# v0_4_6.net
KiCad netlist of a schematic drawn in EAGLE
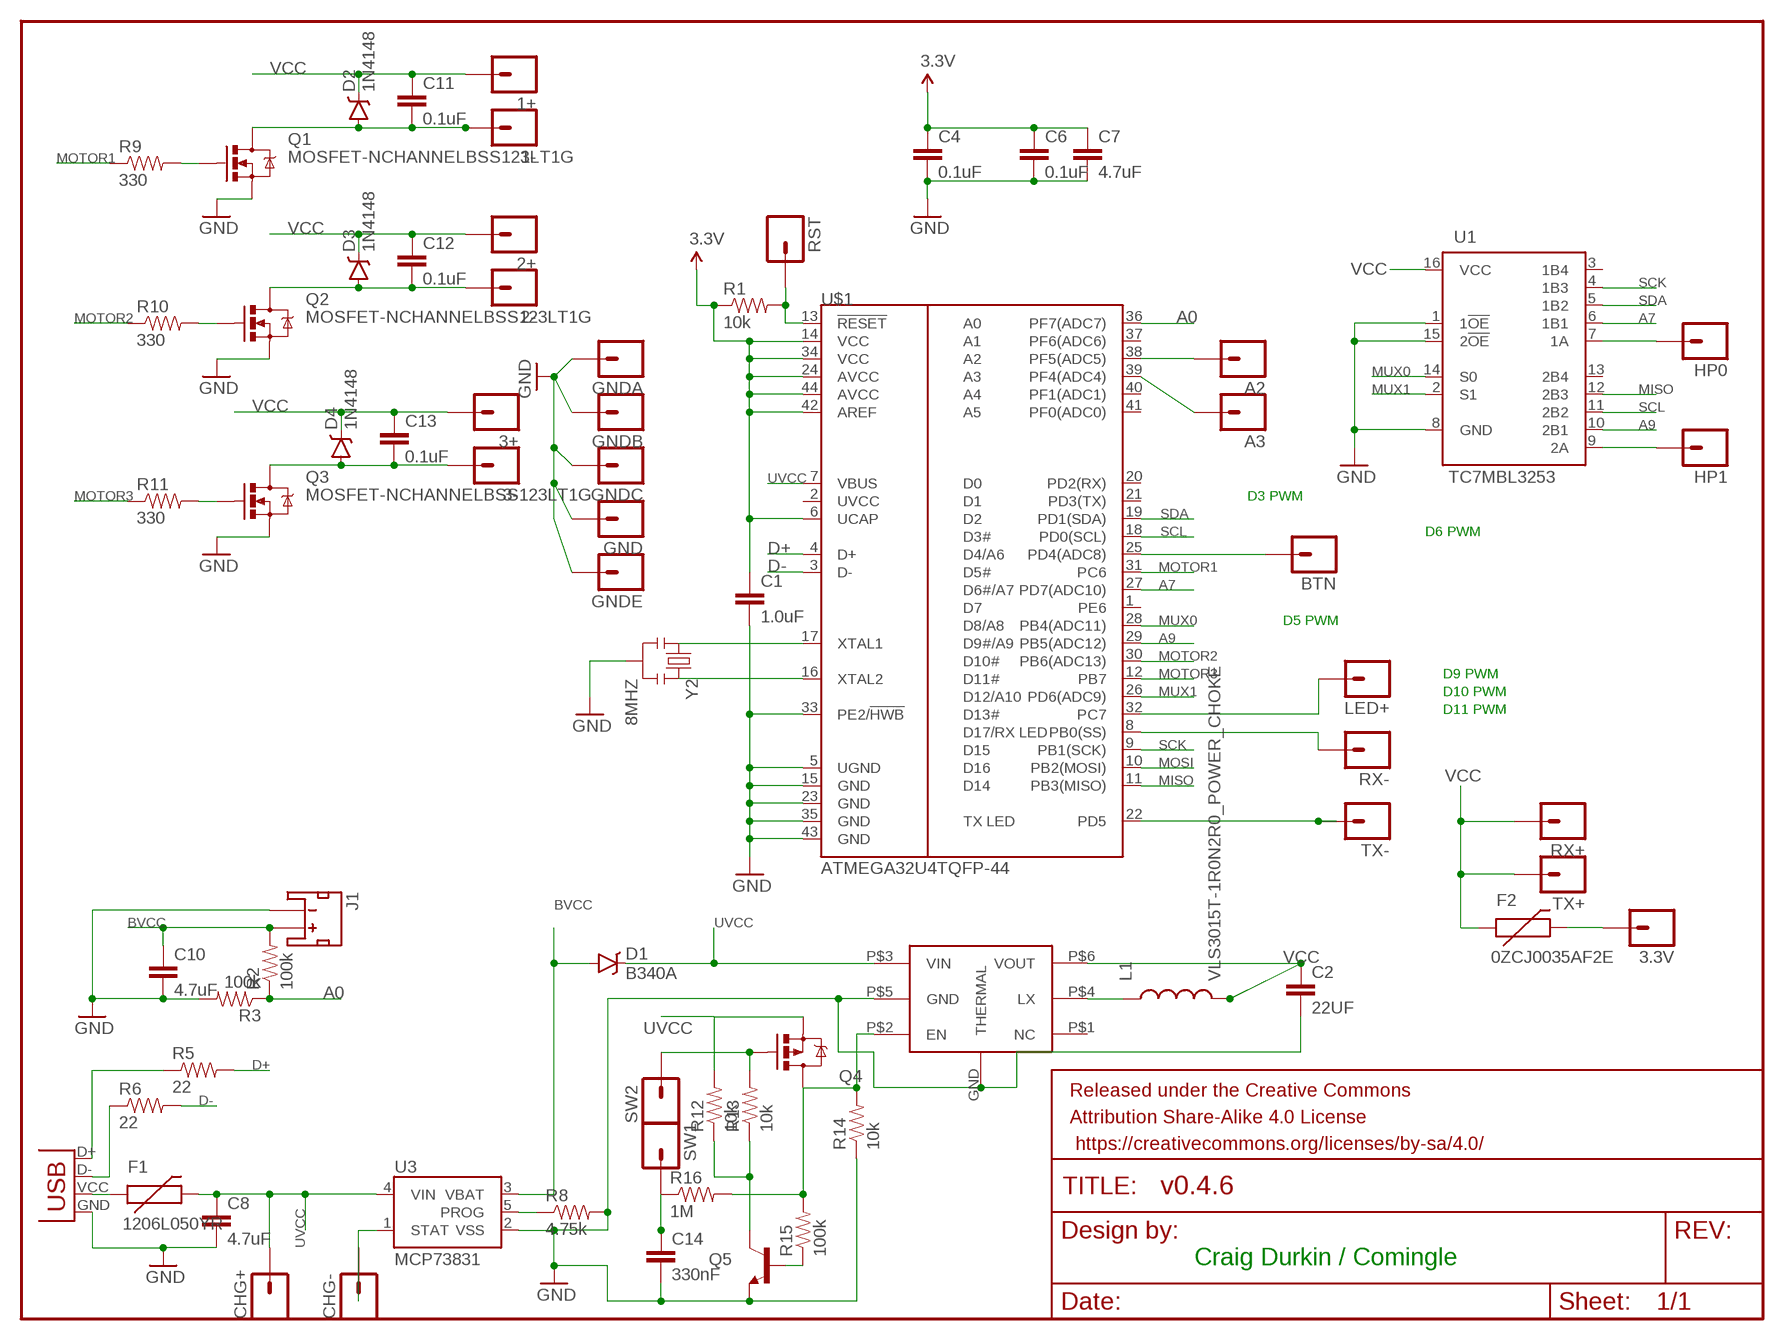
[diagram p0: schematic, sheet 1]

(export (version "E")
  (design (tool "Eeschema 10.0.6"))
  (components
    (comp (ref "1+")
      (value "M01PTH")
      (footprint "eagle-import:1X01")
      (libsource (lib "eagle-import") (part "M01PTH"))
    )
    (comp (ref "1-")
      (value "M01PTH")
      (footprint "eagle-import:1X01")
      (libsource (lib "eagle-import") (part "M01PTH"))
    )
    (comp (ref "2+")
      (value "M01PTH")
      (footprint "eagle-import:1X01")
      (libsource (lib "eagle-import") (part "M01PTH"))
    )
    (comp (ref "2-")
      (value "M01PTH")
      (footprint "eagle-import:1X01")
      (libsource (lib "eagle-import") (part "M01PTH"))
    )
    (comp (ref "3+")
      (value "M01PTH")
      (footprint "eagle-import:1X01")
      (libsource (lib "eagle-import") (part "M01PTH"))
    )
    (comp (ref "3-")
      (value "M01PTH")
      (footprint "eagle-import:1X01")
      (libsource (lib "eagle-import") (part "M01PTH"))
    )
    (comp (ref "3.3V")
      (value "M01PTH")
      (footprint "eagle-import:1X01")
      (libsource (lib "eagle-import") (part "M01PTH"))
    )
    (comp (ref "A2")
      (value "M01PTH")
      (footprint "eagle-import:1X01")
      (libsource (lib "eagle-import") (part "M01PTH"))
    )
    (comp (ref "A3")
      (value "M01PTH")
      (footprint "eagle-import:1X01")
      (libsource (lib "eagle-import") (part "M01PTH"))
    )
    (comp (ref "BTN")
      (value "M01PTH")
      (footprint "eagle-import:1X01")
      (libsource (lib "eagle-import") (part "M01PTH"))
    )
    (comp (ref "C1")
      (value "1.0uF")
      (footprint "eagle-import:0603-CAP")
      (libsource (lib "eagle-import") (part "CAP0603-CAP"))
    )
    (comp (ref "C2")
      (value "22UF")
      (footprint "eagle-import:0805")
      (libsource (lib "eagle-import") (part "v0.4.6_CAP0805"))
    )
    (comp (ref "C4")
      (value "0.1uF")
      (footprint "eagle-import:0603-CAP")
      (libsource (lib "eagle-import") (part "SparkFun-Passives_CAP0603-CAP"))
    )
    (comp (ref "C6")
      (value "0.1uF")
      (footprint "eagle-import:0603-CAP")
      (libsource (lib "eagle-import") (part "SparkFun-Passives_CAP0603-CAP"))
    )
    (comp (ref "C7")
      (value "4.7uF")
      (footprint "eagle-import:0603-CAP")
      (libsource (lib "eagle-import") (part "SparkFun-Passives_CAP0603-CAP"))
    )
    (comp (ref "C8")
      (value "4.7uF")
      (footprint "eagle-import:1206")
      (libsource (lib "eagle-import") (part "SparkFun-Passives_CAP1206"))
    )
    (comp (ref "C10")
      (value "4.7uF")
      (footprint "eagle-import:1206")
      (libsource (lib "eagle-import") (part "SparkFun-Passives_CAP1206"))
    )
    (comp (ref "C11")
      (value "0.1uF")
      (footprint "eagle-import:0603-CAP")
      (libsource (lib "eagle-import") (part "CAP0603-CAP"))
    )
    (comp (ref "C12")
      (value "0.1uF")
      (footprint "eagle-import:0603-CAP")
      (libsource (lib "eagle-import") (part "CAP0603-CAP"))
    )
    (comp (ref "C13")
      (value "0.1uF")
      (footprint "eagle-import:0603-CAP")
      (libsource (lib "eagle-import") (part "CAP0603-CAP"))
    )
    (comp (ref "C14")
      (value "330nF")
      (footprint "eagle-import:0603-CAP")
      (libsource (lib "eagle-import") (part "CAP0603-CAP"))
    )
    (comp (ref "CHG+")
      (value "M01PTH")
      (footprint "eagle-import:1X01")
      (libsource (lib "eagle-import") (part "M01PTH"))
    )
    (comp (ref "CHG-")
      (value "M01PTH")
      (footprint "eagle-import:1X01")
      (libsource (lib "eagle-import") (part "M01PTH"))
    )
    (comp (ref "D1")
      (value "B340A")
      (footprint "eagle-import:SMA-DIODE")
      (libsource (lib "eagle-import") (part "DIODE-SCHOTTKY-B340A"))
    )
    (comp (ref "D2")
      (value "1N4148")
      (footprint "eagle-import:SOD-323")
      (libsource (lib "eagle-import") (part "BAT20JFILM"))
    )
    (comp (ref "D3")
      (value "1N4148")
      (footprint "eagle-import:SOD-323")
      (libsource (lib "eagle-import") (part "BAT20JFILM"))
    )
    (comp (ref "D4")
      (value "1N4148")
      (footprint "eagle-import:SOD-323")
      (libsource (lib "eagle-import") (part "BAT20JFILM"))
    )
    (comp (ref "F1")
      (value "1206L050YR")
      (footprint "eagle-import:PTC-1206")
      (libsource (lib "eagle-import") (part "PTCSMD"))
    )
    (comp (ref "F2")
      (value "0ZCJ0035AF2E")
      (footprint "eagle-import:PTC-1206")
      (libsource (lib "eagle-import") (part "PTCSMD"))
    )
    (comp (ref "FRAME1")
      (value "FRAME-LETTER")
      (footprint "eagle-import:CREATIVE_COMMONS")
      (libsource (lib "eagle-import") (part "FRAME-LETTER"))
    )
    (comp (ref "GND")
      (value "M01PTH")
      (footprint "eagle-import:1X01")
      (libsource (lib "eagle-import") (part "M01PTH"))
    )
    (comp (ref "GNDA")
      (value "M01PTH")
      (footprint "eagle-import:1X01")
      (libsource (lib "eagle-import") (part "M01PTH"))
    )
    (comp (ref "GNDB")
      (value "M01PTH")
      (footprint "eagle-import:1X01")
      (libsource (lib "eagle-import") (part "M01PTH"))
    )
    (comp (ref "GNDC")
      (value "M01PTH")
      (footprint "eagle-import:1X01")
      (libsource (lib "eagle-import") (part "M01PTH"))
    )
    (comp (ref "GNDE")
      (value "M01PTH")
      (footprint "eagle-import:1X01")
      (libsource (lib "eagle-import") (part "M01PTH"))
    )
    (comp (ref "HP0")
      (value "M01PTH")
      (footprint "eagle-import:1X01")
      (libsource (lib "eagle-import") (part "M01PTH"))
    )
    (comp (ref "HP1")
      (value "M01PTH")
      (footprint "eagle-import:1X01")
      (libsource (lib "eagle-import") (part "M01PTH"))
    )
    (comp (ref "J1")
      (value "JST_2MM_MALE")
      (footprint "eagle-import:JST-2-SMD")
      (libsource (lib "eagle-import") (part "JST_2MM_MALE"))
    )
    (comp (ref "JP4")
      (value "USBMICROB-GCT-USB3075")
      (footprint "eagle-import:USB-MICROB-GCT-USB3075")
      (libsource (lib "eagle-import") (part "USBMICROB-GCT-USB3075"))
    )
    (comp (ref "L1")
      (value "VLS3015T-1R0N2R0_POWER_CHOKE")
      (footprint "eagle-import:3MM_POWER_CHOKE")
      (libsource (lib "eagle-import") (part "VLS3015T-1R0N2R0_POWER_CHOKE"))
    )
    (comp (ref "LED+")
      (value "M01PTH")
      (footprint "eagle-import:1X01")
      (libsource (lib "eagle-import") (part "M01PTH"))
    )
    (comp (ref "Q1")
      (value "MOSFET-NCHANNELBSS123LT1G")
      (footprint "eagle-import:SOT23-3")
      (libsource (lib "eagle-import") (part "MOSFET-NCHANNELBSS123LT1G"))
    )
    (comp (ref "Q2")
      (value "MOSFET-NCHANNELBSS123LT1G")
      (footprint "eagle-import:SOT23-3")
      (libsource (lib "eagle-import") (part "MOSFET-NCHANNELBSS123LT1G"))
    )
    (comp (ref "Q3")
      (value "MOSFET-NCHANNELBSS123LT1G")
      (footprint "eagle-import:SOT23-3")
      (libsource (lib "eagle-import") (part "MOSFET-NCHANNELBSS123LT1G"))
    )
    (comp (ref "Q4")
      (value "NTS2101PT1G")
      (footprint "eagle-import:SOT23-3")
      (libsource (lib "eagle-import") (part "MOSFET-PCHANNEL"))
    )
    (comp (ref "Q5")
      (value "MMBT2222A")
      (footprint "eagle-import:SOT23-3")
      (libsource (lib "eagle-import") (part "TRANSISTOR_NPNMMBT2222A"))
    )
    (comp (ref "R1")
      (value "10k")
      (footprint "eagle-import:0603-RES")
      (libsource (lib "eagle-import") (part "RESISTOR0603-RES"))
    )
    (comp (ref "R2")
      (value "100k")
      (footprint "eagle-import:0603-RES")
      (libsource (lib "eagle-import") (part "RESISTOR0603-RES"))
    )
    (comp (ref "R3")
      (value "100k")
      (footprint "eagle-import:0603-RES")
      (libsource (lib "eagle-import") (part "RESISTOR0603-RES"))
    )
    (comp (ref "R5")
      (value "22")
      (footprint "eagle-import:0603-RES")
      (libsource (lib "eagle-import") (part "RESISTOR0603-RES"))
    )
    (comp (ref "R6")
      (value "22")
      (footprint "eagle-import:0603-RES")
      (libsource (lib "eagle-import") (part "RESISTOR0603-RES"))
    )
    (comp (ref "R8")
      (value "4.75k")
      (footprint "eagle-import:0603-RES")
      (libsource (lib "eagle-import") (part "RESISTOR0603-RES"))
    )
    (comp (ref "R9")
      (value "330")
      (footprint "eagle-import:0603-RES")
      (libsource (lib "eagle-import") (part "RESISTOR0603-RES"))
    )
    (comp (ref "R10")
      (value "330")
      (footprint "eagle-import:0603-RES")
      (libsource (lib "eagle-import") (part "RESISTOR0603-RES"))
    )
    (comp (ref "R11")
      (value "330")
      (footprint "eagle-import:0603-RES")
      (libsource (lib "eagle-import") (part "RESISTOR0603-RES"))
    )
    (comp (ref "R12")
      (value "10k")
      (footprint "eagle-import:0603-RES")
      (libsource (lib "eagle-import") (part "RESISTOR0603-RES"))
    )
    (comp (ref "R13")
      (value "10k")
      (footprint "eagle-import:0603-RES")
      (libsource (lib "eagle-import") (part "RESISTOR0603-RES"))
    )
    (comp (ref "R14")
      (value "10k")
      (footprint "eagle-import:0603-RES")
      (libsource (lib "eagle-import") (part "RESISTOR0603-RES"))
    )
    (comp (ref "R15")
      (value "100k")
      (footprint "eagle-import:0603-RES")
      (libsource (lib "eagle-import") (part "RESISTOR0603-RES"))
    )
    (comp (ref "R16")
      (value "1M")
      (footprint "eagle-import:0603-RES")
      (libsource (lib "eagle-import") (part "RESISTOR0603-RES"))
    )
    (comp (ref "RST")
      (value "M01PTH")
      (footprint "eagle-import:1X01")
      (libsource (lib "eagle-import") (part "M01PTH"))
    )
    (comp (ref "RX+")
      (value "M01PTH")
      (footprint "eagle-import:1X01")
      (libsource (lib "eagle-import") (part "M01PTH"))
    )
    (comp (ref "RX-")
      (value "M01PTH")
      (footprint "eagle-import:1X01")
      (libsource (lib "eagle-import") (part "M01PTH"))
    )
    (comp (ref "SW1")
      (value "M01PTH")
      (footprint "eagle-import:1X01")
      (libsource (lib "eagle-import") (part "M01PTH"))
    )
    (comp (ref "SW2")
      (value "M01PTH")
      (footprint "eagle-import:1X01")
      (libsource (lib "eagle-import") (part "M01PTH"))
    )
    (comp (ref "TX+")
      (value "M01PTH")
      (footprint "eagle-import:1X01")
      (libsource (lib "eagle-import") (part "M01PTH"))
    )
    (comp (ref "TX-")
      (value "M01PTH")
      (footprint "eagle-import:1X01")
      (libsource (lib "eagle-import") (part "M01PTH"))
    )
    (comp (ref "U$1")
      (value "ATMEGA32U4TQFP-44")
      (footprint "eagle-import:TQFP44")
      (libsource (lib "eagle-import") (part "ATMEGA32U4TQFP-44"))
    )
    (comp (ref "U$3")
      (value "SC189")
      (footprint "eagle-import:MLPD-UT6")
      (libsource (lib "eagle-import") (part "SC189"))
    )
    (comp (ref "U1")
      (value "TC7MBL3253")
      (footprint "eagle-import:SSOP16-PRACTICE")
      (libsource (lib "eagle-import") (part "TC7MBL3253"))
    )
    (comp (ref "U3")
      (value "MCP73831")
      (footprint "eagle-import:SOT23-5")
      (libsource (lib "eagle-import") (part "MCP73831"))
    )
    (comp (ref "Y2")
      (value "8MHZ")
      (footprint "eagle-import:RESONATOR-SMD")
      (libsource (lib "eagle-import") (part "RESONATOR8MHZ"))
    )
  )
  (nets
    (net (code "1") (name "/A0") (class "Default")
      (node (ref "R2") (pin "1") (pinfunction "1_1") (pintype "passive"))
      (node (ref "R3") (pin "1") (pinfunction "1_1") (pintype "passive"))
      (node (ref "U$1") (pin "36") (pinfunction "PF7(ADC7)_36") (pintype "bidirectional"))
    )
    (net (code "2") (name "/A7") (class "Default")
      (node (ref "U$1") (pin "27") (pinfunction "PD7(ADC10)_27") (pintype "bidirectional"))
      (node (ref "U1") (pin "6") (pinfunction "1B1_6") (pintype "bidirectional"))
    )
    (net (code "3") (name "/A9") (class "Default")
      (node (ref "U$1") (pin "29") (pinfunction "PB5(ADC12)_29") (pintype "bidirectional"))
      (node (ref "U1") (pin "10") (pinfunction "2B1_10") (pintype "bidirectional"))
    )
    (net (code "4") (name "/BVCC") (class "Default")
      (node (ref "C10") (pin "1") (pinfunction "1_1") (pintype "passive"))
      (node (ref "D1") (pin "A") (pinfunction "A_A") (pintype "passive"))
      (node (ref "J1") (pin "2") (pinfunction "+_2") (pintype "bidirectional"))
      (node (ref "R2") (pin "2") (pinfunction "2_2") (pintype "passive"))
      (node (ref "U3") (pin "3") (pinfunction "VBAT_3") (pintype "power_in"))
    )
    (net (code "5") (name "/D+") (class "Default")
      (node (ref "R5") (pin "2") (pinfunction "2_2") (pintype "passive"))
      (node (ref "U$1") (pin "4") (pinfunction "D+_4") (pintype "bidirectional"))
    )
    (net (code "6") (name "/D-") (class "Default")
      (node (ref "R6") (pin "2") (pinfunction "2_2") (pintype "passive"))
      (node (ref "U$1") (pin "3") (pinfunction "D-_3") (pintype "bidirectional"))
    )
    (net (code "7") (name "/MISO") (class "Default")
      (node (ref "U$1") (pin "11") (pinfunction "PB3(MISO)_11") (pintype "bidirectional"))
      (node (ref "U1") (pin "12") (pinfunction "2B3_12") (pintype "bidirectional"))
    )
    (net (code "8") (name "/MOSI") (class "Default")
      (node (ref "U$1") (pin "10") (pinfunction "PB2(MOSI)_10") (pintype "bidirectional"))
    )
    (net (code "9") (name "/MOTOR1") (class "Default")
      (node (ref "R9") (pin "1") (pinfunction "1_1") (pintype "passive"))
      (node (ref "U$1") (pin "31") (pinfunction "PC6_31") (pintype "bidirectional"))
    )
    (net (code "10") (name "/MOTOR2") (class "Default")
      (node (ref "R10") (pin "1") (pinfunction "1_1") (pintype "passive"))
      (node (ref "U$1") (pin "30") (pinfunction "PB6(ADC13)_30") (pintype "bidirectional"))
    )
    (net (code "11") (name "/MOTOR3") (class "Default")
      (node (ref "R11") (pin "1") (pinfunction "1_1") (pintype "passive"))
      (node (ref "U$1") (pin "12") (pinfunction "PB7_12") (pintype "bidirectional"))
    )
    (net (code "12") (name "/MUX0") (class "Default")
      (node (ref "U$1") (pin "28") (pinfunction "PB4(ADC11)_28") (pintype "bidirectional"))
      (node (ref "U1") (pin "14") (pinfunction "S0_14") (pintype "bidirectional"))
    )
    (net (code "13") (name "/MUX1") (class "Default")
      (node (ref "U$1") (pin "26") (pinfunction "PD6(ADC9)_26") (pintype "bidirectional"))
      (node (ref "U1") (pin "2") (pinfunction "S1_2") (pintype "bidirectional"))
    )
    (net (code "14") (name "/SCK") (class "Default")
      (node (ref "U$1") (pin "9") (pinfunction "PB1(SCK)_9") (pintype "bidirectional"))
      (node (ref "U1") (pin "4") (pinfunction "1B3_4") (pintype "bidirectional"))
    )
    (net (code "15") (name "/SCL") (class "Default")
      (node (ref "U$1") (pin "18") (pinfunction "PD0(SCL)_18") (pintype "bidirectional"))
      (node (ref "U1") (pin "11") (pinfunction "2B2_11") (pintype "bidirectional"))
    )
    (net (code "16") (name "/SDA") (class "Default")
      (node (ref "U$1") (pin "19") (pinfunction "PD1(SDA)_19") (pintype "bidirectional"))
      (node (ref "U1") (pin "5") (pinfunction "1B2_5") (pintype "bidirectional"))
    )
    (net (code "17") (name "/UVCC") (class "Default")
      (node (ref "C8") (pin "1") (pinfunction "1_1") (pintype "passive"))
      (node (ref "CHG+") (pin "1") (pinfunction "1_1") (pintype "passive"))
      (node (ref "D1") (pin "C") (pinfunction "C_C") (pintype "passive"))
      (node (ref "F1") (pin "2") (pinfunction "2_2") (pintype "bidirectional"))
      (node (ref "Q4") (pin "2") (pinfunction "S_2") (pintype "passive"))
      (node (ref "R12") (pin "2") (pinfunction "2_2") (pintype "passive"))
      (node (ref "U$1") (pin "7") (pinfunction "VBUS_7") (pintype "bidirectional"))
      (node (ref "U$3") (pin "P$3") (pinfunction "VIN_P$3") (pintype "power_in"))
      (node (ref "U3") (pin "4") (pinfunction "VIN_4") (pintype "power_in"))
    )
    (net (code "18") (name "3.3V") (class "Default")
      (node (ref "1+") (pin "1") (pinfunction "1_1") (pintype "passive"))
      (node (ref "2+") (pin "1") (pinfunction "1_1") (pintype "passive"))
      (node (ref "3+") (pin "1") (pinfunction "1_1") (pintype "passive"))
      (node (ref "C1") (pin "1") (pinfunction "1_1") (pintype "passive"))
      (node (ref "C11") (pin "1") (pinfunction "1_1") (pintype "passive"))
      (node (ref "C12") (pin "1") (pinfunction "1_1") (pintype "passive"))
      (node (ref "C13") (pin "1") (pinfunction "1_1") (pintype "passive"))
      (node (ref "C2") (pin "1") (pinfunction "1_1") (pintype "passive"))
      (node (ref "C4") (pin "1") (pinfunction "1_1") (pintype "passive"))
      (node (ref "C6") (pin "1") (pinfunction "1_1") (pintype "passive"))
      (node (ref "C7") (pin "1") (pinfunction "1_1") (pintype "passive"))
      (node (ref "D2") (pin "C") (pinfunction "C_C") (pintype "passive"))
      (node (ref "D3") (pin "C") (pinfunction "C_C") (pintype "passive"))
      (node (ref "D4") (pin "C") (pinfunction "C_C") (pintype "passive"))
      (node (ref "F2") (pin "1") (pinfunction "1_1") (pintype "bidirectional"))
      (node (ref "L1") (pin "2") (pinfunction "2_2") (pintype "passive"))
      (node (ref "R1") (pin "1") (pinfunction "1_1") (pintype "passive"))
      (node (ref "RX+") (pin "1") (pinfunction "1_1") (pintype "passive"))
      (node (ref "TX+") (pin "1") (pinfunction "1_1") (pintype "passive"))
      (node (ref "U$1") (pin "14") (pinfunction "VCC_14") (pintype "bidirectional"))
      (node (ref "U$1") (pin "24") (pinfunction "AVCC_24") (pintype "bidirectional"))
      (node (ref "U$1") (pin "34") (pinfunction "VCC_34") (pintype "bidirectional"))
      (node (ref "U$1") (pin "42") (pinfunction "AREF_42") (pintype "bidirectional"))
      (node (ref "U$1") (pin "44") (pinfunction "AVCC_44") (pintype "bidirectional"))
      (node (ref "U$1") (pin "6") (pinfunction "UCAP_6") (pintype "bidirectional"))
      (node (ref "U$3") (pin "P$6") (pinfunction "VOUT_P$6") (pintype "output"))
      (node (ref "U1") (pin "16") (pinfunction "VCC_16") (pintype "power_in"))
    )
    (net (code "19") (name "GND") (class "Default")
      (node (ref "C1") (pin "2") (pinfunction "2_2") (pintype "passive"))
      (node (ref "C10") (pin "2") (pinfunction "2_2") (pintype "passive"))
      (node (ref "C14") (pin "2") (pinfunction "2_2") (pintype "passive"))
      (node (ref "C2") (pin "2") (pinfunction "2_2") (pintype "passive"))
      (node (ref "C4") (pin "2") (pinfunction "2_2") (pintype "passive"))
      (node (ref "C6") (pin "2") (pinfunction "2_2") (pintype "passive"))
      (node (ref "C7") (pin "2") (pinfunction "2_2") (pintype "passive"))
      (node (ref "C8") (pin "2") (pinfunction "2_2") (pintype "passive"))
      (node (ref "GND") (pin "1") (pinfunction "1_1") (pintype "passive"))
      (node (ref "GNDA") (pin "1") (pinfunction "1_1") (pintype "passive"))
      (node (ref "GNDB") (pin "1") (pinfunction "1_1") (pintype "passive"))
      (node (ref "GNDC") (pin "1") (pinfunction "1_1") (pintype "passive"))
      (node (ref "GNDE") (pin "1") (pinfunction "1_1") (pintype "passive"))
      (node (ref "J1") (pin "1") (pinfunction "-_1") (pintype "bidirectional"))
      (node (ref "JP4") (pin "GND") (pinfunction "GND_GND") (pintype "bidirectional"))
      (node (ref "Q1") (pin "2") (pinfunction "S_2") (pintype "passive"))
      (node (ref "Q2") (pin "2") (pinfunction "S_2") (pintype "passive"))
      (node (ref "Q3") (pin "2") (pinfunction "S_2") (pintype "passive"))
      (node (ref "Q5") (pin "2") (pinfunction "E_2") (pintype "passive"))
      (node (ref "R14") (pin "1") (pinfunction "1_1") (pintype "passive"))
      (node (ref "R3") (pin "2") (pinfunction "2_2") (pintype "passive"))
      (node (ref "R8") (pin "2") (pinfunction "2_2") (pintype "passive"))
      (node (ref "U$1") (pin "15") (pinfunction "GND_15") (pintype "bidirectional"))
      (node (ref "U$1") (pin "23") (pinfunction "GND_23") (pintype "bidirectional"))
      (node (ref "U$1") (pin "33") (pinfunction "PE2/~{HWB}_33") (pintype "bidirectional"))
      (node (ref "U$1") (pin "35") (pinfunction "GND_35") (pintype "bidirectional"))
      (node (ref "U$1") (pin "43") (pinfunction "GND_43") (pintype "bidirectional"))
      (node (ref "U$1") (pin "5") (pinfunction "UGND_5") (pintype "bidirectional"))
      (node (ref "U$3") (pin "GND") (pinfunction "THERMAL_GND") (pintype "power_in"))
      (node (ref "U$3") (pin "P$5") (pinfunction "GND_P$5") (pintype "power_in"))
      (node (ref "U1") (pin "1") (pinfunction "1~{OE}_1") (pintype "input"))
      (node (ref "U1") (pin "15") (pinfunction "2~{OE}_15") (pintype "input"))
      (node (ref "U1") (pin "8") (pinfunction "GND_8") (pintype "power_in"))
      (node (ref "U3") (pin "2") (pinfunction "VSS_2") (pintype "power_in"))
      (node (ref "Y2") (pin "2") (pinfunction "2_2") (pintype "passive"))
    )
    (net (code "20") (name "Net-(3.3V-Pad1)") (class "Default")
      (node (ref "3.3V") (pin "1") (pinfunction "1_1") (pintype "passive"))
      (node (ref "F2") (pin "2") (pinfunction "2_2") (pintype "bidirectional"))
    )
    (net (code "21") (name "Net-(C14-Pad1)") (class "Default")
      (node (ref "C14") (pin "1") (pinfunction "1_1") (pintype "passive"))
      (node (ref "R16") (pin "1") (pinfunction "1_1") (pintype "passive"))
      (node (ref "SW1") (pin "1") (pinfunction "1_1") (pintype "passive"))
    )
    (net (code "22") (name "Net-(JP4-PadD+)") (class "Default")
      (node (ref "JP4") (pin "D+") (pinfunction "D+_D+") (pintype "bidirectional"))
      (node (ref "R5") (pin "1") (pinfunction "1_1") (pintype "passive"))
    )
    (net (code "23") (name "Net-(JP4-PadD-)") (class "Default")
      (node (ref "JP4") (pin "D-") (pinfunction "D-_D-") (pintype "bidirectional"))
      (node (ref "R6") (pin "1") (pinfunction "1_1") (pintype "passive"))
    )
    (net (code "24") (name "Net-(JP4-VBUS)") (class "Default")
      (node (ref "F1") (pin "1") (pinfunction "1_1") (pintype "bidirectional"))
      (node (ref "JP4") (pin "VCC") (pinfunction "VBUS_VCC") (pintype "bidirectional"))
    )
    (net (code "25") (name "Net-(Q1-D)") (class "Default")
      (node (ref "1-") (pin "1") (pinfunction "1_1") (pintype "passive"))
      (node (ref "C11") (pin "2") (pinfunction "2_2") (pintype "passive"))
      (node (ref "D2") (pin "A") (pinfunction "A_A") (pintype "passive"))
      (node (ref "Q1") (pin "3") (pinfunction "D_3") (pintype "passive"))
    )
    (net (code "26") (name "Net-(Q1-G)") (class "Default")
      (node (ref "Q1") (pin "1") (pinfunction "G_1") (pintype "passive"))
      (node (ref "R9") (pin "2") (pinfunction "2_2") (pintype "passive"))
    )
    (net (code "27") (name "Net-(Q2-D)") (class "Default")
      (node (ref "2-") (pin "1") (pinfunction "1_1") (pintype "passive"))
      (node (ref "C12") (pin "2") (pinfunction "2_2") (pintype "passive"))
      (node (ref "D3") (pin "A") (pinfunction "A_A") (pintype "passive"))
      (node (ref "Q2") (pin "3") (pinfunction "D_3") (pintype "passive"))
    )
    (net (code "28") (name "Net-(Q2-G)") (class "Default")
      (node (ref "Q2") (pin "1") (pinfunction "G_1") (pintype "passive"))
      (node (ref "R10") (pin "2") (pinfunction "2_2") (pintype "passive"))
    )
    (net (code "29") (name "Net-(Q3-D)") (class "Default")
      (node (ref "3-") (pin "1") (pinfunction "1_1") (pintype "passive"))
      (node (ref "C13") (pin "2") (pinfunction "2_2") (pintype "passive"))
      (node (ref "D4") (pin "A") (pinfunction "A_A") (pintype "passive"))
      (node (ref "Q3") (pin "3") (pinfunction "D_3") (pintype "passive"))
    )
    (net (code "30") (name "Net-(Q3-G)") (class "Default")
      (node (ref "Q3") (pin "1") (pinfunction "G_1") (pintype "passive"))
      (node (ref "R11") (pin "2") (pinfunction "2_2") (pintype "passive"))
    )
    (net (code "31") (name "Net-(Q4-D)") (class "Default")
      (node (ref "Q4") (pin "3") (pinfunction "D_3") (pintype "passive"))
      (node (ref "R14") (pin "2") (pinfunction "2_2") (pintype "passive"))
      (node (ref "R15") (pin "2") (pinfunction "2_2") (pintype "passive"))
      (node (ref "R16") (pin "2") (pinfunction "2_2") (pintype "passive"))
      (node (ref "U$3") (pin "P$2") (pinfunction "EN_P$2") (pintype "input"))
    )
    (net (code "32") (name "Net-(Q4-G)") (class "Default")
      (node (ref "Q4") (pin "1") (pinfunction "G_1") (pintype "passive"))
      (node (ref "R13") (pin "2") (pinfunction "2_2") (pintype "passive"))
      (node (ref "SW2") (pin "1") (pinfunction "1_1") (pintype "passive"))
    )
    (net (code "33") (name "Net-(Q5-B)") (class "Default")
      (node (ref "Q5") (pin "1") (pinfunction "B_1") (pintype "passive"))
      (node (ref "R15") (pin "1") (pinfunction "1_1") (pintype "passive"))
    )
    (net (code "34") (name "Net-(Q5-C)") (class "Default")
      (node (ref "Q5") (pin "3") (pinfunction "C_3") (pintype "passive"))
      (node (ref "R12") (pin "1") (pinfunction "1_1") (pintype "passive"))
      (node (ref "R13") (pin "1") (pinfunction "1_1") (pintype "passive"))
    )
    (net (code "35") (name "Net-(U$1-PB0(SS))") (class "Default")
      (node (ref "RX-") (pin "1") (pinfunction "1_1") (pintype "passive"))
      (node (ref "U$1") (pin "8") (pinfunction "PB0(SS)_8") (pintype "bidirectional"))
    )
    (net (code "36") (name "Net-(U$1-PC7)") (class "Default")
      (node (ref "LED+") (pin "1") (pinfunction "1_1") (pintype "passive"))
      (node (ref "U$1") (pin "32") (pinfunction "PC7_32") (pintype "bidirectional"))
    )
    (net (code "37") (name "Net-(U$1-PD4(ADC8))") (class "Default")
      (node (ref "BTN") (pin "1") (pinfunction "1_1") (pintype "passive"))
      (node (ref "U$1") (pin "25") (pinfunction "PD4(ADC8)_25") (pintype "bidirectional"))
    )
    (net (code "38") (name "Net-(U$1-PD5)") (class "Default")
      (node (ref "TX-") (pin "1") (pinfunction "1_1") (pintype "passive"))
      (node (ref "U$1") (pin "22") (pinfunction "PD5_22") (pintype "bidirectional"))
    )
    (net (code "39") (name "Net-(U$1-PF4(ADC4))") (class "Default")
      (node (ref "A3") (pin "1") (pinfunction "1_1") (pintype "passive"))
      (node (ref "U$1") (pin "39") (pinfunction "PF4(ADC4)_39") (pintype "bidirectional"))
    )
    (net (code "40") (name "Net-(U$1-PF5(ADC5))") (class "Default")
      (node (ref "A2") (pin "1") (pinfunction "1_1") (pintype "passive"))
      (node (ref "U$1") (pin "38") (pinfunction "PF5(ADC5)_38") (pintype "bidirectional"))
    )
    (net (code "41") (name "Net-(U$1-XTAL1)") (class "Default")
      (node (ref "U$1") (pin "17") (pinfunction "XTAL1_17") (pintype "bidirectional"))
      (node (ref "Y2") (pin "1") (pinfunction "1_1") (pintype "passive"))
    )
    (net (code "42") (name "Net-(U$1-XTAL2)") (class "Default")
      (node (ref "U$1") (pin "16") (pinfunction "XTAL2_16") (pintype "bidirectional"))
      (node (ref "Y2") (pin "3") (pinfunction "3_3") (pintype "passive"))
    )
    (net (code "43") (name "Net-(U$1-~{RESET})") (class "Default")
      (node (ref "R1") (pin "2") (pinfunction "2_2") (pintype "passive"))
      (node (ref "RST") (pin "1") (pinfunction "1_1") (pintype "passive"))
      (node (ref "U$1") (pin "13") (pinfunction "~{RESET}_13") (pintype "bidirectional"))
    )
    (net (code "44") (name "Net-(U$3-LX)") (class "Default")
      (node (ref "L1") (pin "1") (pinfunction "1_1") (pintype "passive"))
      (node (ref "U$3") (pin "P$4") (pinfunction "LX_P$4") (pintype "passive"))
    )
    (net (code "45") (name "Net-(U1-1A)") (class "Default")
      (node (ref "HP0") (pin "1") (pinfunction "1_1") (pintype "passive"))
      (node (ref "U1") (pin "7") (pinfunction "1A_7") (pintype "bidirectional"))
    )
    (net (code "46") (name "Net-(U1-2A)") (class "Default")
      (node (ref "HP1") (pin "1") (pinfunction "1_1") (pintype "passive"))
      (node (ref "U1") (pin "9") (pinfunction "2A_9") (pintype "bidirectional"))
    )
    (net (code "47") (name "Net-(U3-PROG)") (class "Default")
      (node (ref "R8") (pin "1") (pinfunction "1_1") (pintype "passive"))
      (node (ref "U3") (pin "5") (pinfunction "PROG_5") (pintype "bidirectional"))
    )
    (net (code "48") (name "Net-(U3-STAT)") (class "Default")
      (node (ref "CHG-") (pin "1") (pinfunction "1_1") (pintype "passive"))
      (node (ref "U3") (pin "1") (pinfunction "STAT_1") (pintype "output"))
    )
    (net (code "49") (name "unconnected-(J1-PAD1-PadNC1)") (class "Default")
      (node (ref "J1") (pin "NC1") (pinfunction "PAD1_NC1") (pintype "bidirectional"))
    )
    (net (code "50") (name "unconnected-(J1-PAD2-PadNC2)") (class "Default")
      (node (ref "J1") (pin "NC2") (pinfunction "PAD2_NC2") (pintype "bidirectional"))
    )
    (net (code "51") (name "unconnected-(U$1-PD2(RX)-Pad20)") (class "Default")
      (node (ref "U$1") (pin "20") (pinfunction "PD2(RX)_20") (pintype "bidirectional"))
    )
    (net (code "52") (name "unconnected-(U$1-PD3(TX)-Pad21)") (class "Default")
      (node (ref "U$1") (pin "21") (pinfunction "PD3(TX)_21") (pintype "bidirectional"))
    )
    (net (code "53") (name "unconnected-(U$1-PE6-Pad1)") (class "Default")
      (node (ref "U$1") (pin "1") (pinfunction "PE6_1") (pintype "bidirectional"))
    )
    (net (code "54") (name "unconnected-(U$1-PF0(ADC0)-Pad41)") (class "Default")
      (node (ref "U$1") (pin "41") (pinfunction "PF0(ADC0)_41") (pintype "bidirectional"))
    )
    (net (code "55") (name "unconnected-(U$1-PF1(ADC1)-Pad40)") (class "Default")
      (node (ref "U$1") (pin "40") (pinfunction "PF1(ADC1)_40") (pintype "bidirectional"))
    )
    (net (code "56") (name "unconnected-(U$1-PF6(ADC6)-Pad37)") (class "Default")
      (node (ref "U$1") (pin "37") (pinfunction "PF6(ADC6)_37") (pintype "bidirectional"))
    )
    (net (code "57") (name "unconnected-(U$1-UVCC-Pad2)") (class "Default")
      (node (ref "U$1") (pin "2") (pinfunction "UVCC_2") (pintype "bidirectional"))
    )
    (net (code "58") (name "unconnected-(U$3-NC-PadP$1)") (class "Default")
      (node (ref "U$3") (pin "P$1") (pinfunction "NC_P$1") (pintype "no_connect"))
    )
    (net (code "59") (name "unconnected-(U1-1B4-Pad3)") (class "Default")
      (node (ref "U1") (pin "3") (pinfunction "1B4_3") (pintype "bidirectional"))
    )
    (net (code "60") (name "unconnected-(U1-2B4-Pad13)") (class "Default")
      (node (ref "U1") (pin "13") (pinfunction "2B4_13") (pintype "bidirectional"))
    )
  )
)
